# altium_kicad.net
KiCad netlist of a schematic drawn in Altium Designer
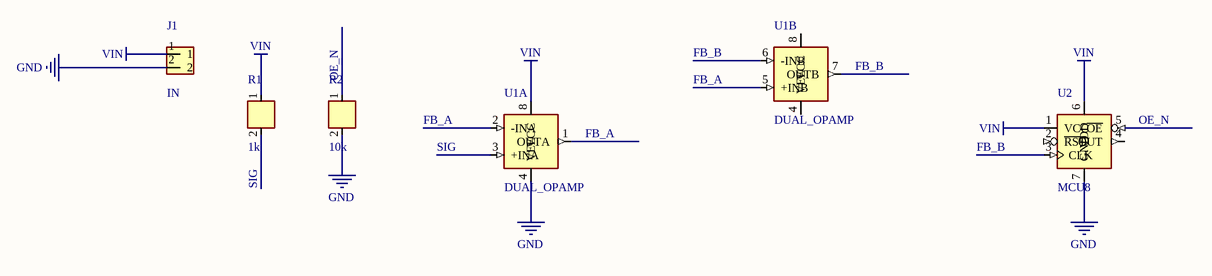
[diagram p0: altium_kicad.SchDoc]

(export (version "E")
  (design (tool "Eeschema 10.0.6"))
  (components
    (comp (ref "J1")
      (value "IN")
      (footprint "FenoliteDemo:PinHeader_1x02")
      (libsource (lib "altium_kicad") (part "CONN2"))
    )
    (comp (ref "R1")
      (value "1k")
      (footprint "FenoliteDemo:R0603")
      (libsource (lib "altium_kicad") (part "R_V"))
    )
    (comp (ref "R2")
      (value "10k")
      (footprint "FenoliteDemo:R0603")
      (libsource (lib "altium_kicad") (part "R_V"))
    )
    (comp (ref "U1")
      (value "DUAL_OPAMP")
      (footprint "FenoliteDemo:SOIC8")
      (libsource (lib "altium_kicad") (part "DUAL_OPAMP"))
    )
    (comp (ref "U2")
      (value "MCU8")
      (footprint "FenoliteDemo:SOIC8")
      (libsource (lib "altium_kicad") (part "MCU8"))
    )
  )
  (nets
    (net (code "1") (name "/FB_A") (class "Default")
      (node (ref "U1") (pin "1") (pinfunction "OUTA_1") (pintype "output"))
      (node (ref "U1") (pin "2") (pinfunction "-INA_2") (pintype "input"))
      (node (ref "U1") (pin "5") (pinfunction "+INB_5") (pintype "input"))
    )
    (net (code "2") (name "/FB_B") (class "Default")
      (node (ref "U1") (pin "6") (pinfunction "-INB_6") (pintype "input"))
      (node (ref "U1") (pin "7") (pinfunction "OUTB_7") (pintype "output"))
      (node (ref "U2") (pin "3") (pinfunction "CLK_3") (pintype "input"))
    )
    (net (code "3") (name "/OE_N") (class "Default")
      (node (ref "R2") (pin "1") (pinfunction "~_1") (pintype "passive"))
      (node (ref "U2") (pin "5") (pinfunction "~{OE}_5") (pintype "input"))
    )
    (net (code "4") (name "/SIG") (class "Default")
      (node (ref "R1") (pin "2") (pinfunction "~_2") (pintype "passive"))
      (node (ref "U1") (pin "3") (pinfunction "+INA_3") (pintype "input"))
    )
    (net (code "5") (name "GND") (class "Default")
      (node (ref "J1") (pin "2") (pinfunction "2_2") (pintype "passive"))
      (node (ref "R2") (pin "2") (pinfunction "~_2") (pintype "passive"))
      (node (ref "U1") (pin "4") (pinfunction "VEE_4") (pintype "power_in"))
      (node (ref "U2") (pin "7") (pinfunction "GND_7") (pintype "power_in"))
    )
    (net (code "6") (name "VIN") (class "Default")
      (node (ref "J1") (pin "1") (pinfunction "1_1") (pintype "passive"))
      (node (ref "R1") (pin "1") (pinfunction "~_1") (pintype "passive"))
      (node (ref "U1") (pin "8") (pinfunction "VCC_8") (pintype "power_in"))
      (node (ref "U2") (pin "1") (pinfunction "VCC_1") (pintype "power_in"))
      (node (ref "U2") (pin "6") (pinfunction "VDD_6") (pintype "power_in"))
    )
    (net (code "7") (name "unconnected-(U1B-VCC-Pad8)") (class "Default")
      (node (ref "U1") (pin "8") (pinfunction "VCC_8") (pintype "power_in"))
    )
    (net (code "8") (name "unconnected-(U1B-VEE-Pad4)") (class "Default")
      (node (ref "U1") (pin "4") (pinfunction "VEE_4") (pintype "power_in"))
    )
    (net (code "9") (name "unconnected-(U2-OUT-Pad4)") (class "Default")
      (node (ref "U2") (pin "4") (pinfunction "OUT_4") (pintype "output"))
    )
    (net (code "10") (name "unconnected-(U2-TP-Pad8)") (class "Default")
      (node (ref "U2") (pin "8") (pinfunction "TP_8") (pintype "passive"))
    )
    (net (code "11") (name "unconnected-(U2-~{RST}-Pad2)") (class "Default")
      (node (ref "U2") (pin "2") (pinfunction "~{RST}_2") (pintype "input"))
    )
  )
)
